# 2Timer.net
KiCad netlist of a schematic drawn in EAGLE
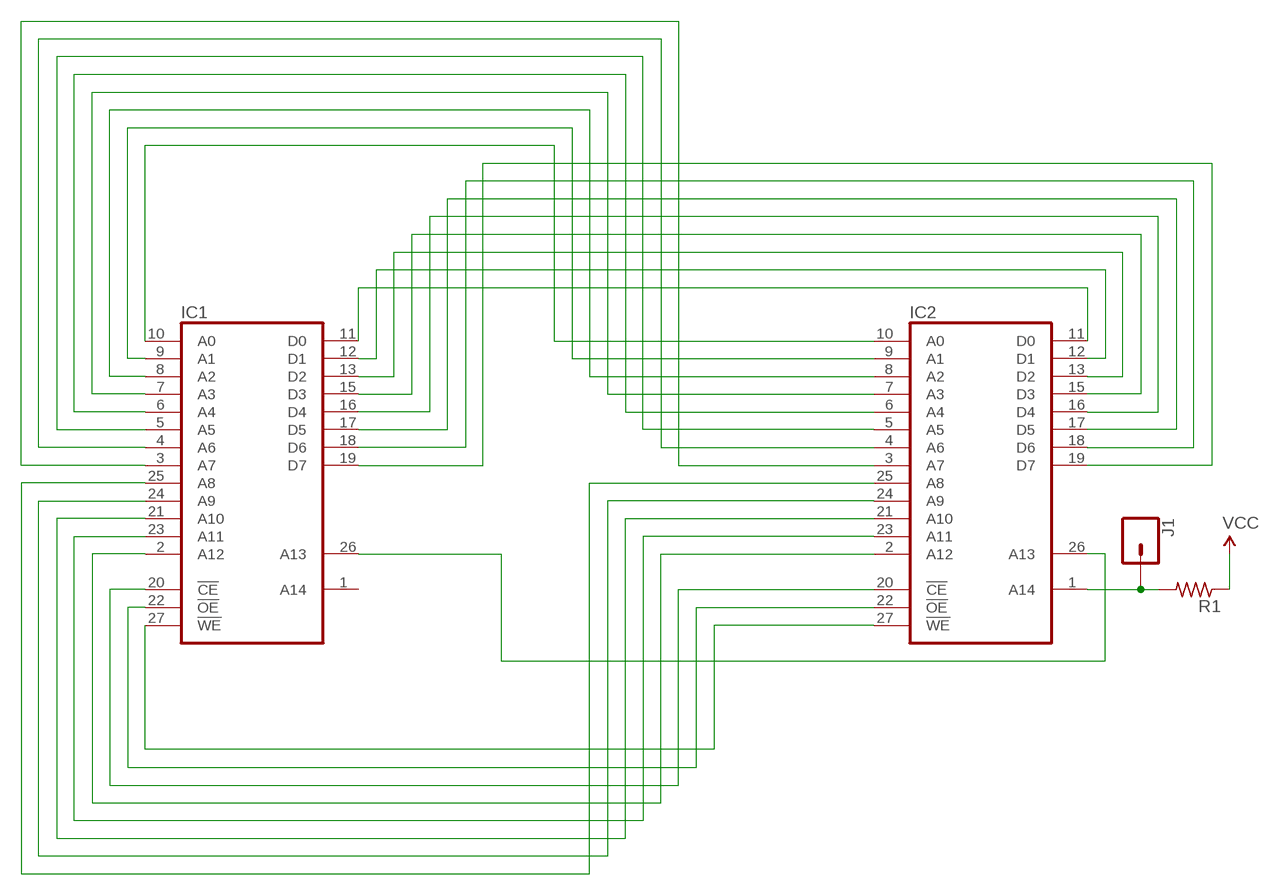
[diagram p0: schematic, sheet 1]

(export (version "E")
  (design (tool "Eeschema 10.0.6"))
  (components
    (comp (ref "IC1")
      (value "2864")
      (footprint "eagle-import:DIL28")
      (libsource (lib "eagle-import") (part "2864"))
    )
    (comp (ref "IC2")
      (value "2864")
      (footprint "eagle-import:DIL28")
      (libsource (lib "eagle-import") (part "2864"))
    )
    (comp (ref "J1")
      (value "CONN_01")
      (footprint "eagle-import:1X01")
      (libsource (lib "eagle-import") (part "CONN_01"))
    )
    (comp (ref "R1")
      (value "R-US_0204/5")
      (footprint "eagle-import:0204_5")
      (libsource (lib "eagle-import") (part "R-US_0204/5"))
    )
  )
  (nets
    (net (code "1") (name "Net-(IC1A-A0)") (class "Default")
      (node (ref "IC1") (pin "10") (pinfunction "A0_10") (pintype "input"))
      (node (ref "IC2") (pin "10") (pinfunction "A0_10") (pintype "input"))
    )
    (net (code "2") (name "Net-(IC1A-A1)") (class "Default")
      (node (ref "IC1") (pin "9") (pinfunction "A1_9") (pintype "input"))
      (node (ref "IC2") (pin "9") (pinfunction "A1_9") (pintype "input"))
    )
    (net (code "3") (name "Net-(IC1A-A2)") (class "Default")
      (node (ref "IC1") (pin "8") (pinfunction "A2_8") (pintype "input"))
      (node (ref "IC2") (pin "8") (pinfunction "A2_8") (pintype "input"))
    )
    (net (code "4") (name "Net-(IC1A-A3)") (class "Default")
      (node (ref "IC1") (pin "7") (pinfunction "A3_7") (pintype "input"))
      (node (ref "IC2") (pin "7") (pinfunction "A3_7") (pintype "input"))
    )
    (net (code "5") (name "Net-(IC1A-A4)") (class "Default")
      (node (ref "IC1") (pin "6") (pinfunction "A4_6") (pintype "input"))
      (node (ref "IC2") (pin "6") (pinfunction "A4_6") (pintype "input"))
    )
    (net (code "6") (name "Net-(IC1A-A5)") (class "Default")
      (node (ref "IC1") (pin "5") (pinfunction "A5_5") (pintype "input"))
      (node (ref "IC2") (pin "5") (pinfunction "A5_5") (pintype "input"))
    )
    (net (code "7") (name "Net-(IC1A-A6)") (class "Default")
      (node (ref "IC1") (pin "4") (pinfunction "A6_4") (pintype "input"))
      (node (ref "IC2") (pin "4") (pinfunction "A6_4") (pintype "input"))
    )
    (net (code "8") (name "Net-(IC1A-A7)") (class "Default")
      (node (ref "IC1") (pin "3") (pinfunction "A7_3") (pintype "input"))
      (node (ref "IC2") (pin "3") (pinfunction "A7_3") (pintype "input"))
    )
    (net (code "9") (name "Net-(IC1A-A8)") (class "Default")
      (node (ref "IC1") (pin "25") (pinfunction "A8_25") (pintype "input"))
      (node (ref "IC2") (pin "25") (pinfunction "A8_25") (pintype "input"))
    )
    (net (code "10") (name "Net-(IC1A-A9)") (class "Default")
      (node (ref "IC1") (pin "24") (pinfunction "A9_24") (pintype "input"))
      (node (ref "IC2") (pin "24") (pinfunction "A9_24") (pintype "input"))
    )
    (net (code "11") (name "Net-(IC1A-A10)") (class "Default")
      (node (ref "IC1") (pin "21") (pinfunction "A10_21") (pintype "input"))
      (node (ref "IC2") (pin "21") (pinfunction "A10_21") (pintype "input"))
    )
    (net (code "12") (name "Net-(IC1A-A11)") (class "Default")
      (node (ref "IC1") (pin "23") (pinfunction "A11_23") (pintype "input"))
      (node (ref "IC2") (pin "23") (pinfunction "A11_23") (pintype "input"))
    )
    (net (code "13") (name "Net-(IC1A-A12)") (class "Default")
      (node (ref "IC1") (pin "2") (pinfunction "A12_2") (pintype "input"))
      (node (ref "IC2") (pin "2") (pinfunction "A12_2") (pintype "input"))
    )
    (net (code "14") (name "Net-(IC1A-A13)") (class "Default")
      (node (ref "IC1") (pin "26") (pinfunction "A13_26") (pintype "input"))
      (node (ref "IC2") (pin "26") (pinfunction "A13_26") (pintype "input"))
    )
    (net (code "15") (name "Net-(IC1A-D0)") (class "Default")
      (node (ref "IC1") (pin "11") (pinfunction "D0_11") (pintype "bidirectional"))
      (node (ref "IC2") (pin "11") (pinfunction "D0_11") (pintype "bidirectional"))
    )
    (net (code "16") (name "Net-(IC1A-D1)") (class "Default")
      (node (ref "IC1") (pin "12") (pinfunction "D1_12") (pintype "bidirectional"))
      (node (ref "IC2") (pin "12") (pinfunction "D1_12") (pintype "bidirectional"))
    )
    (net (code "17") (name "Net-(IC1A-D2)") (class "Default")
      (node (ref "IC1") (pin "13") (pinfunction "D2_13") (pintype "bidirectional"))
      (node (ref "IC2") (pin "13") (pinfunction "D2_13") (pintype "bidirectional"))
    )
    (net (code "18") (name "Net-(IC1A-D3)") (class "Default")
      (node (ref "IC1") (pin "15") (pinfunction "D3_15") (pintype "bidirectional"))
      (node (ref "IC2") (pin "15") (pinfunction "D3_15") (pintype "bidirectional"))
    )
    (net (code "19") (name "Net-(IC1A-D4)") (class "Default")
      (node (ref "IC1") (pin "16") (pinfunction "D4_16") (pintype "bidirectional"))
      (node (ref "IC2") (pin "16") (pinfunction "D4_16") (pintype "bidirectional"))
    )
    (net (code "20") (name "Net-(IC1A-D5)") (class "Default")
      (node (ref "IC1") (pin "17") (pinfunction "D5_17") (pintype "bidirectional"))
      (node (ref "IC2") (pin "17") (pinfunction "D5_17") (pintype "bidirectional"))
    )
    (net (code "21") (name "Net-(IC1A-D6)") (class "Default")
      (node (ref "IC1") (pin "18") (pinfunction "D6_18") (pintype "bidirectional"))
      (node (ref "IC2") (pin "18") (pinfunction "D6_18") (pintype "bidirectional"))
    )
    (net (code "22") (name "Net-(IC1A-D7)") (class "Default")
      (node (ref "IC1") (pin "19") (pinfunction "D7_19") (pintype "bidirectional"))
      (node (ref "IC2") (pin "19") (pinfunction "D7_19") (pintype "bidirectional"))
    )
    (net (code "23") (name "Net-(IC1A-~{CE})") (class "Default")
      (node (ref "IC1") (pin "20") (pinfunction "~{CE}_20") (pintype "input"))
      (node (ref "IC2") (pin "20") (pinfunction "~{CE}_20") (pintype "input"))
    )
    (net (code "24") (name "Net-(IC1A-~{OE})") (class "Default")
      (node (ref "IC1") (pin "22") (pinfunction "~{OE}_22") (pintype "input"))
      (node (ref "IC2") (pin "22") (pinfunction "~{OE}_22") (pintype "input"))
    )
    (net (code "25") (name "Net-(IC1A-~{WE})") (class "Default")
      (node (ref "IC1") (pin "27") (pinfunction "~{WE}_27") (pintype "input"))
      (node (ref "IC2") (pin "27") (pinfunction "~{WE}_27") (pintype "input"))
    )
    (net (code "26") (name "Net-(IC2A-A14)") (class "Default")
      (node (ref "IC2") (pin "1") (pinfunction "A14_1") (pintype "input"))
      (node (ref "J1") (pin "1") (pinfunction "1_1") (pintype "passive"))
      (node (ref "R1") (pin "2") (pinfunction "2_2") (pintype "passive"))
    )
    (net (code "27") (name "VCC") (class "Default")
      (node (ref "R1") (pin "1") (pinfunction "1_1") (pintype "passive"))
    )
    (net (code "28") (name "unconnected-(IC1A-A14-Pad1)") (class "Default")
      (node (ref "IC1") (pin "1") (pinfunction "A14_1") (pintype "input"))
    )
  )
)
